# xbee_reciever_and_main.net
KiCad netlist of a schematic drawn in Altium Designer
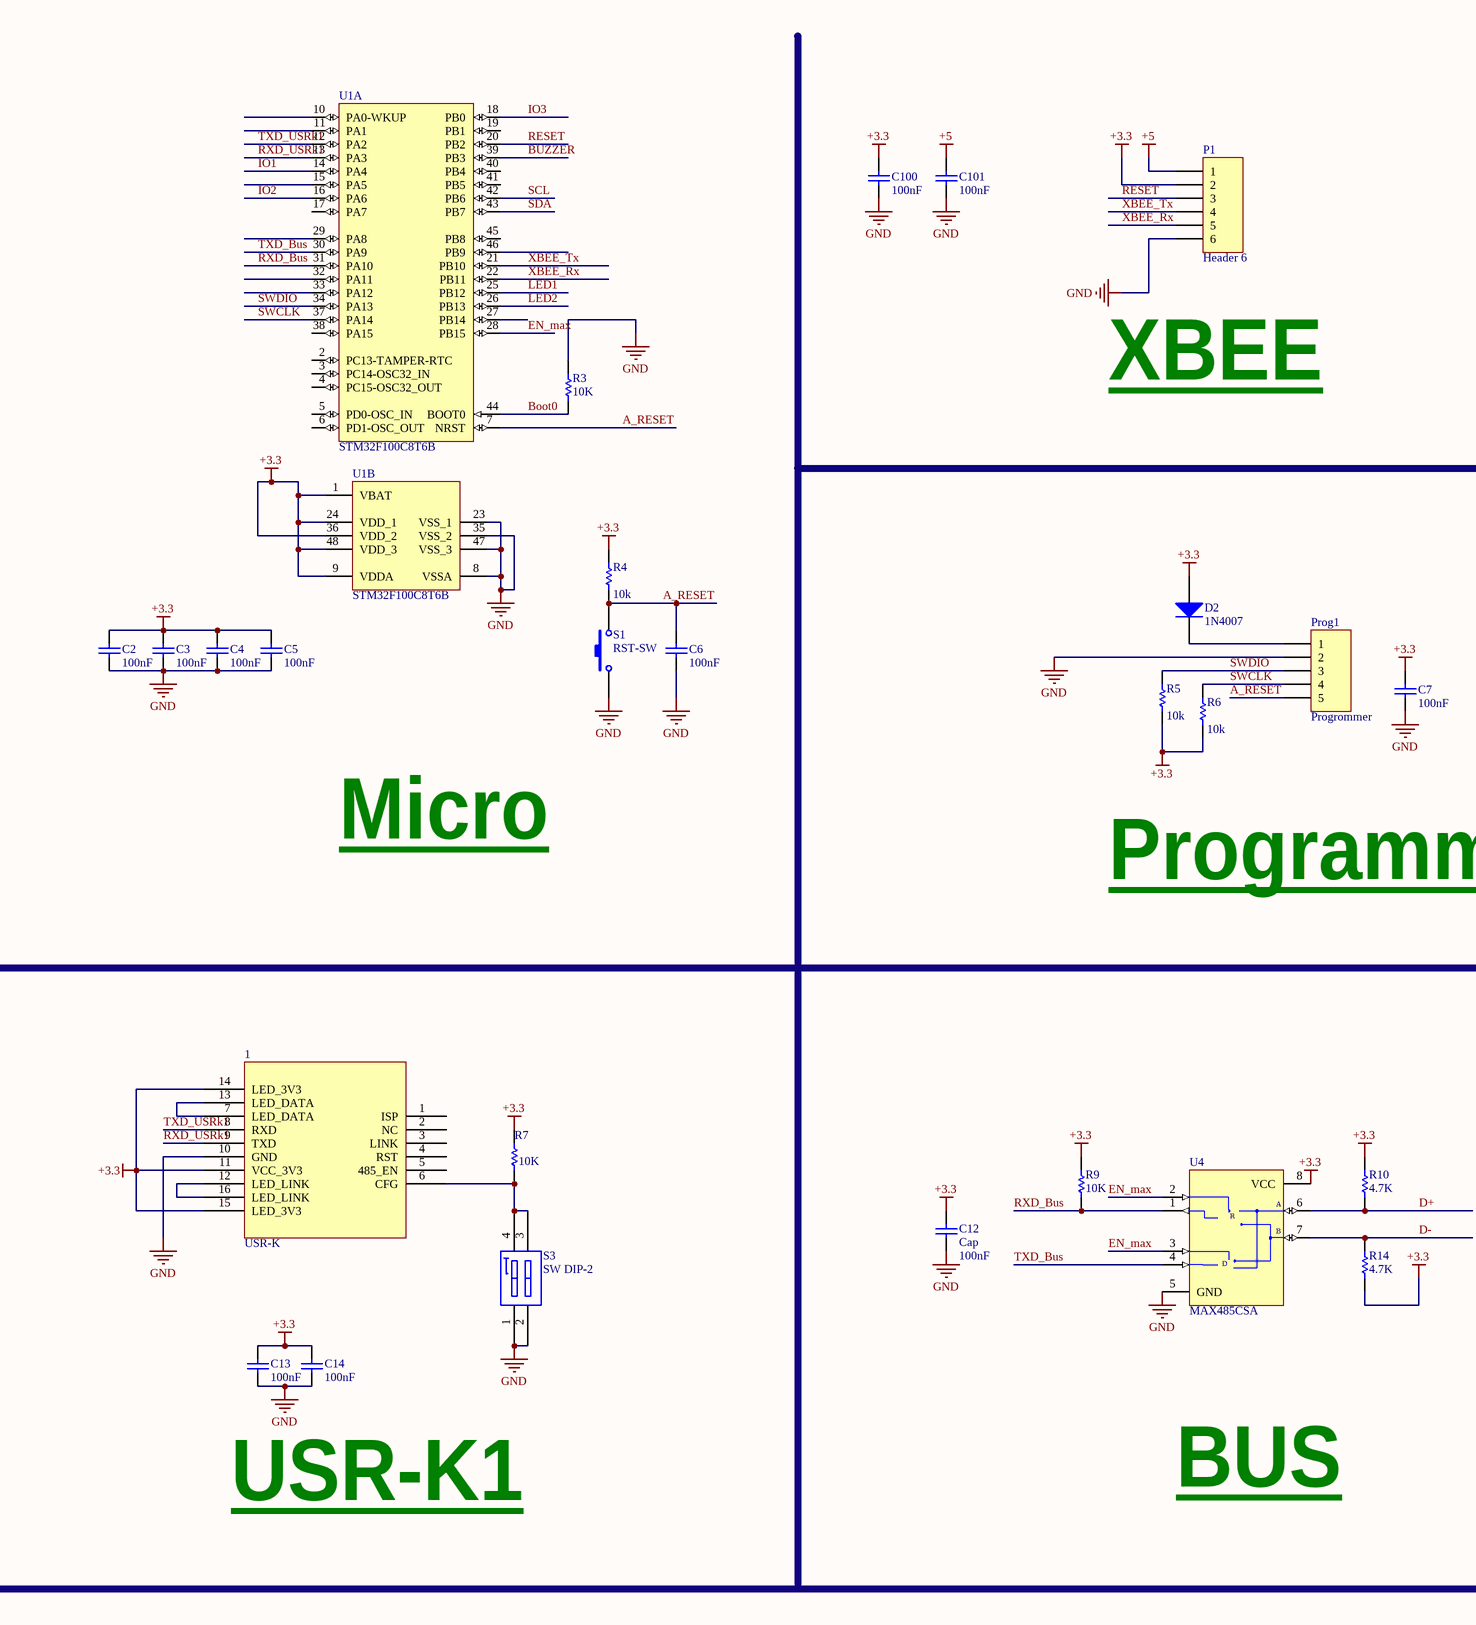
[diagram p0: xbee reciever and main.SchDoc, left]
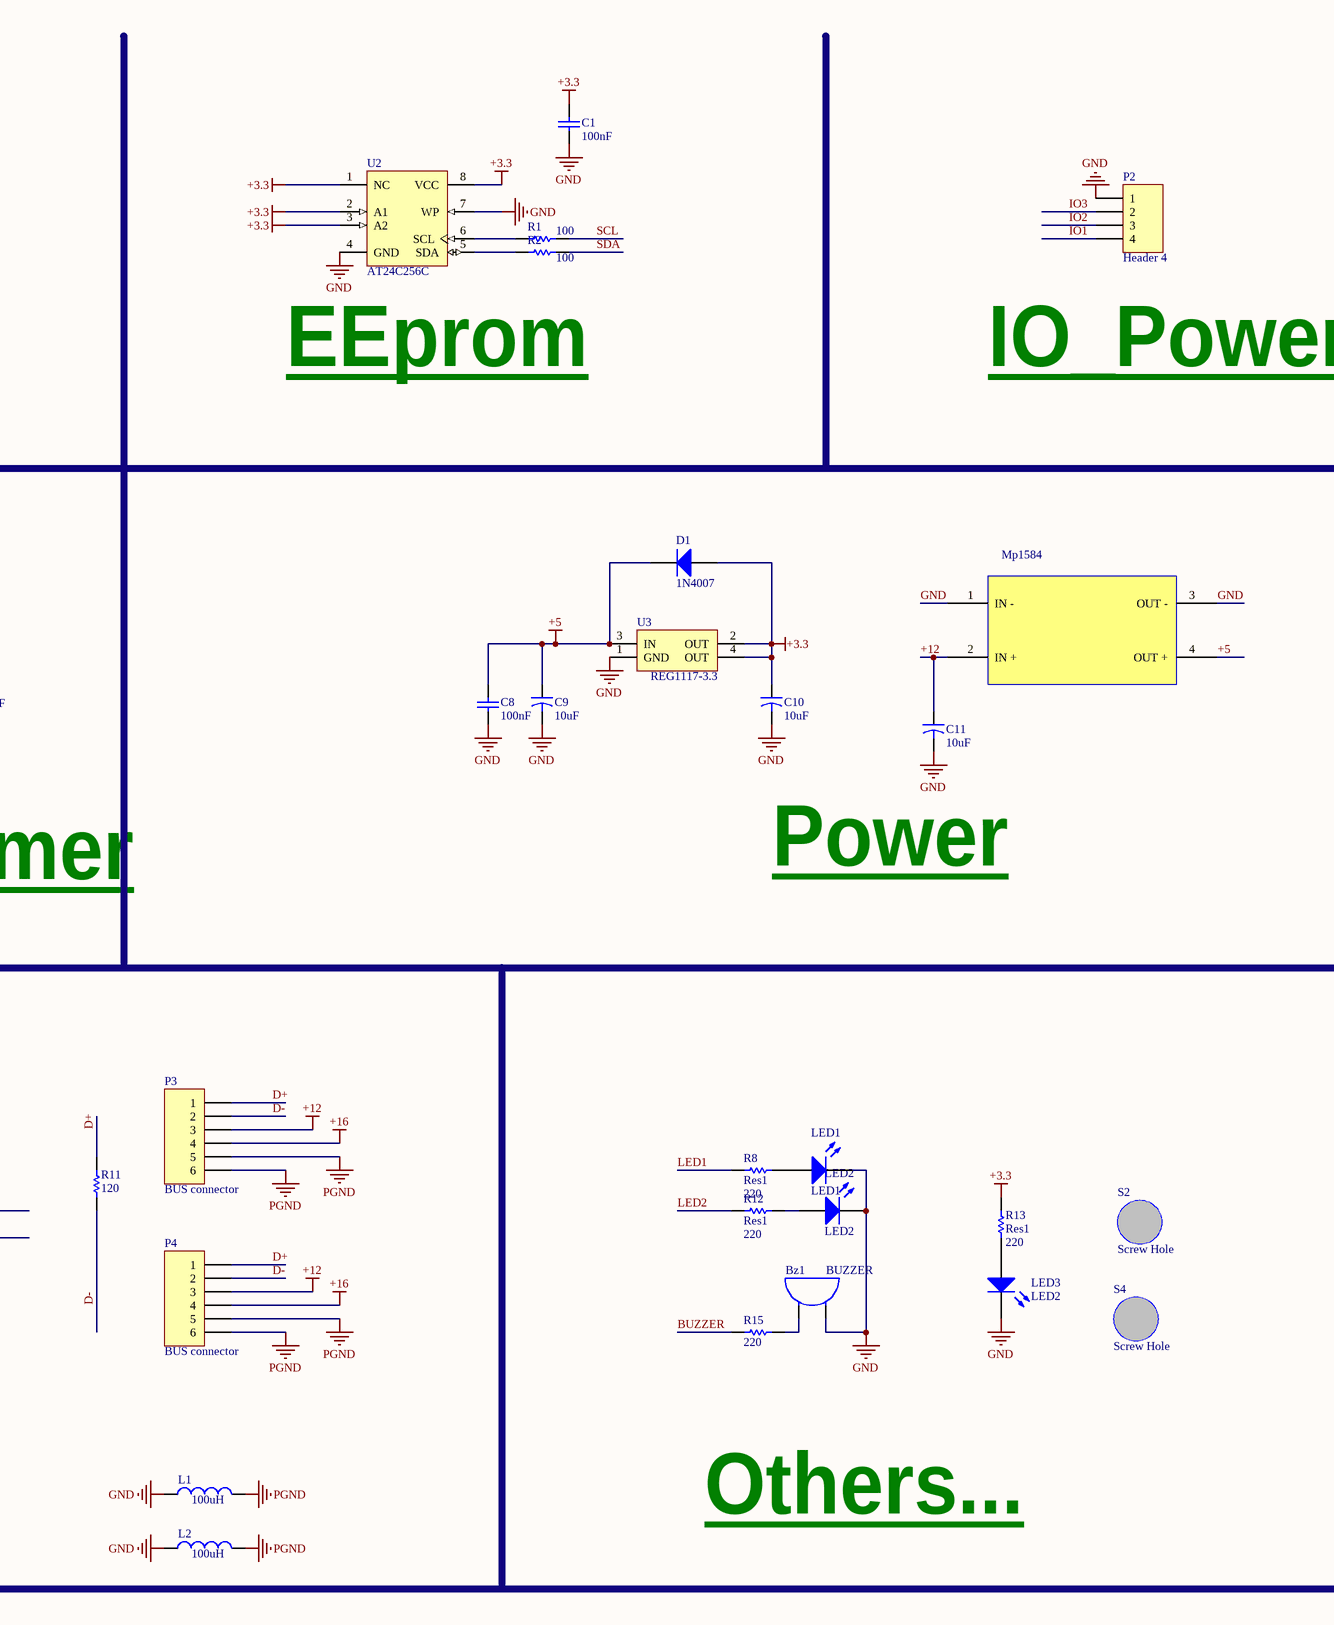
[diagram p1: xbee reciever and main.SchDoc, right]

(export (version "E")
  (design (tool "Eeschema 10.0.6"))
  (components
    (comp (ref "1") (value "USR-K") (footprint "USR-K1") (libsource (lib "USR-K1") (part "USR-K")))
    (comp (ref "Bz1") (value "BUZZER") (footprint "BUZZER") (libsource (lib "Device") (part "BUZZER")))
    (comp (ref "C1")
      (value "100nF")
      (footprint "1608[0603]")
      (description "Capacitor")
      (fields
        (field (name "MANUFACTURER") "Generic Components")
        (field (name "PUBLISHER") "Altium Hobart Technology Centre")
      )
      (libsource (lib "Miscellaneous Devices") (part "Cap"))
    )
    (comp (ref "C2")
      (value "100nF")
      (footprint "1608[0603]")
      (description "Capacitor")
      (fields
        (field (name "MANUFACTURER") "Generic Components")
        (field (name "PUBLISHER") "Altium Hobart Technology Centre")
      )
      (libsource (lib "Miscellaneous Devices") (part "Cap"))
    )
    (comp (ref "C3")
      (value "100nF")
      (footprint "1608[0603]")
      (description "Capacitor")
      (fields
        (field (name "MANUFACTURER") "Generic Components")
        (field (name "PUBLISHER") "Altium Hobart Technology Centre")
      )
      (libsource (lib "Miscellaneous Devices") (part "Cap"))
    )
    (comp (ref "C4")
      (value "100nF")
      (footprint "1608[0603]")
      (description "Capacitor")
      (fields
        (field (name "MANUFACTURER") "Generic Components")
        (field (name "PUBLISHER") "Altium Hobart Technology Centre")
      )
      (libsource (lib "Miscellaneous Devices") (part "Cap"))
    )
    (comp (ref "C5")
      (value "100nF")
      (footprint "1608[0603]")
      (description "Capacitor")
      (fields
        (field (name "MANUFACTURER") "Generic Components")
        (field (name "PUBLISHER") "Altium Hobart Technology Centre")
      )
      (libsource (lib "Miscellaneous Devices") (part "Cap"))
    )
    (comp (ref "C6")
      (value "100nF")
      (footprint "1608[0603]")
      (description "Capacitor")
      (fields
        (field (name "MANUFACTURER") "Generic Components")
        (field (name "PUBLISHER") "Altium Hobart Technology Centre")
      )
      (libsource (lib "Miscellaneous Devices") (part "Cap"))
    )
    (comp (ref "C7")
      (value "100nF")
      (footprint "j1-0603")
      (description "Capacitor")
      (fields
        (field (name "MANUFACTURER") "Generic Components")
        (field (name "PUBLISHER") "Altium Hobart Technology Centre")
      )
      (libsource (lib "Miscellaneous Devices") (part "Cap"))
    )
    (comp (ref "C8")
      (value "100nF")
      (footprint "J1-0603")
      (description "Capacitor")
      (fields (field (name "PUBLISHER") "Altium Limited"))
      (libsource (lib "Miscellaneous Devices") (part "Cap"))
    )
    (comp (ref "C9")
      (value "10uF")
      (footprint "2012[0805]")
      (description "Capacitor")
      (fields (field (name "Comment") "Cap_El") (field (name "PUBLISHER") "Altium Limited"))
      (libsource (lib "KN2CLib") (part "Cap_El"))
    )
    (comp (ref "C10")
      (value "10uF")
      (footprint "2012[0805]")
      (description "Capacitor")
      (fields (field (name "Comment") "Cap_El") (field (name "PUBLISHER") "Altium Limited"))
      (libsource (lib "KN2CLib") (part "Cap_El"))
    )
    (comp (ref "C11")
      (value "10uF")
      (footprint "2012[0805]")
      (description "Capacitor")
      (fields (field (name "Comment") "Cap_El") (field (name "PUBLISHER") "Altium Limited"))
      (libsource (lib "KN2CLib") (part "Cap_El"))
    )
    (comp (ref "C12")
      (value "Cap")
      (footprint "j1-0603")
      (description "Capacitor")
      (fields (field (name "ALTIUM_VALUE") "100nF") (field (name "PUBLISHER") "Altium Limited"))
      (libsource (lib "Miscellaneous Devices") (part "Cap"))
    )
    (comp (ref "C13")
      (value "100nF")
      (footprint "J1-0603")
      (description "Capacitor")
      (fields (field (name "PUBLISHER") "Altium Limited"))
      (libsource (lib "Miscellaneous Devices") (part "Cap"))
    )
    (comp (ref "C14")
      (value "100nF")
      (footprint "J1-0603")
      (description "Capacitor")
      (fields (field (name "PUBLISHER") "Altium Limited"))
      (libsource (lib "Miscellaneous Devices") (part "Cap"))
    )
    (comp (ref "C100")
      (value "100nF")
      (footprint "1608[0603]")
      (description "Capacitor")
      (fields
        (field (name "MANUFACTURER") "Generic Components")
        (field (name "PUBLISHER") "Altium Hobart Technology Centre")
      )
      (libsource (lib "Miscellaneous Devices") (part "Cap"))
    )
    (comp (ref "C101")
      (value "100nF")
      (footprint "1608[0603]")
      (description "Capacitor")
      (fields
        (field (name "MANUFACTURER") "Generic Components")
        (field (name "PUBLISHER") "Altium Hobart Technology Centre")
      )
      (libsource (lib "Miscellaneous Devices") (part "Cap"))
    )
    (comp (ref "D1")
      (value "1N4007")
      (footprint "US1M")
      (description "1 Amp General Purpose Rectifier")
      (fields (field (name "PUBLISHER") "Altium Limited"))
      (libsource (lib "KN2CLib") (part "Diode"))
    )
    (comp (ref "D2")
      (value "1N4007")
      (footprint "US1M")
      (description "1 Amp General Purpose Rectifier")
      (fields (field (name "PUBLISHER") "Altium Limited"))
      (libsource (lib "KN2CLib") (part "Diode"))
    )
    (comp (ref "L1")
      (value "100uH")
      (footprint "2012[0805]")
      (description "Inductor")
      (fields
        (field (name "MANUFACTURER") "Generic Components")
        (field (name "PUBLISHER") "Altium Hobart Technology Centre")
      )
      (libsource (lib "Miscellaneous Devices") (part "Inductor"))
    )
    (comp (ref "L2")
      (value "100uH")
      (footprint "2012[0805]")
      (description "Inductor")
      (fields
        (field (name "MANUFACTURER") "Generic Components")
        (field (name "PUBLISHER") "Altium Hobart Technology Centre")
      )
      (libsource (lib "Miscellaneous Devices") (part "Inductor"))
    )
    (comp (ref "LED1")
      (value "LED1")
      (footprint "3518")
      (description "Typical BLUE SiC LED")
      (fields (field (name "PUBLISHER") "Altium Limited"))
      (libsource (lib "Miscellaneous Devices") (part "LED3"))
    )
    (comp (ref "LED2")
      (value "LED2")
      (footprint "3518")
      (description "Typical BLUE SiC LED")
      (fields (field (name "PUBLISHER") "Altium Limited"))
      (libsource (lib "Miscellaneous Devices") (part "LED3"))
    )
    (comp (ref "LED3")
      (value "LED2")
      (footprint "3518")
      (description "Typical BLUE SiC LED")
      (fields (field (name "PUBLISHER") "Altium Limited"))
      (libsource (lib "Miscellaneous Devices") (part "LED3"))
    )
    (comp (ref "Mp1") (value "Mp1584") (footprint "mp1584-1.8") (libsource (lib "mehdi2309") (part "Mp1584")))
    (comp (ref "P1")
      (value "Header 6")
      (footprint "HDR1X6")
      (description "Header, 6-Pin")
      (fields (field (name "PUBLISHER") "Altium Limited"))
      (libsource (lib "") (part "Header 6_1"))
    )
    (comp (ref "P2")
      (value "Header 4")
      (footprint "JP circular 4")
      (description "Header, 4-Pin")
      (fields (field (name "PUBLISHER") "Altium Limited"))
      (libsource (lib "Miscellaneous Connectors") (part "Header 4"))
    )
    (comp (ref "P3")
      (value "BUS connector")
      (footprint "CON6-TIWAN")
      (description "Header, 6-Pin")
      (fields (field (name "PUBLISHER") "Altium Limited"))
      (libsource (lib "Miscellaneous Connectors") (part "Header 6"))
    )
    (comp (ref "P4")
      (value "BUS connector")
      (footprint "con6-tiwan")
      (description "Header, 6-Pin")
      (fields (field (name "PUBLISHER") "Altium Limited"))
      (libsource (lib "Miscellaneous Connectors") (part "Header 6"))
    )
    (comp (ref "Prog1")
      (value "Progrommer")
      (footprint "HDR1x5")
      (description "Header, 5-Pin")
      (fields (field (name "PUBLISHER") "Altium Limited"))
      (libsource (lib "Miscellaneous Connectors") (part "Header 5"))
    )
    (comp (ref "R1")
      (value "100")
      (footprint "j1-0603")
      (description "Resistor")
      (fields (field (name "Comment") "Res1") (field (name "PUBLISHER") "Altium Limited"))
      (libsource (lib "Miscellaneous Devices") (part "Res1"))
    )
    (comp (ref "R2")
      (value "100")
      (footprint "j1-0603")
      (description "Resistor")
      (fields (field (name "Comment") "Res1") (field (name "PUBLISHER") "Altium Limited"))
      (libsource (lib "Miscellaneous Devices") (part "Res1"))
    )
    (comp (ref "R3")
      (value "10K")
      (footprint "J1-0603")
      (description "Resistor")
      (fields (field (name "PUBLISHER") "Altium Limited"))
      (libsource (lib "Miscellaneous Devices") (part "Res1"))
    )
    (comp (ref "R4")
      (value "10k")
      (footprint "J1-0603")
      (description "Semiconductor Resistor")
      (fields (field (name "PUBLISHER") "Altium Limited"))
      (libsource (lib "KN2CLib") (part "Res"))
    )
    (comp (ref "R5")
      (value "10k")
      (footprint "J1-0603")
      (description "Semiconductor Resistor")
      (fields (field (name "PUBLISHER") "Altium Limited"))
      (libsource (lib "KN2CLib") (part "Res"))
    )
    (comp (ref "R6")
      (value "10k")
      (footprint "J1-0603")
      (description "Semiconductor Resistor")
      (fields (field (name "PUBLISHER") "Altium Limited"))
      (libsource (lib "KN2CLib") (part "Res"))
    )
    (comp (ref "R7")
      (value "10K")
      (footprint "J1-0603")
      (description "Resistor")
      (fields (field (name "PUBLISHER") "Altium Limited"))
      (libsource (lib "Miscellaneous Devices") (part "Res1"))
    )
    (comp (ref "R8")
      (value "Res1")
      (footprint "j1-0603")
      (description "Resistor")
      (fields (field (name "ALTIUM_VALUE") "220") (field (name "PUBLISHER") "Altium Limited"))
      (libsource (lib "Miscellaneous Devices") (part "Res1"))
    )
    (comp (ref "R9")
      (value "10K")
      (footprint "j1-0603")
      (description "Resistor")
      (fields (field (name "Comment") "Res1") (field (name "PUBLISHER") "Altium Limited"))
      (libsource (lib "Miscellaneous Devices") (part "Res1"))
    )
    (comp (ref "R10")
      (value "4.7K")
      (footprint "j1-0603")
      (description "Resistor")
      (fields (field (name "Comment") "Res1") (field (name "PUBLISHER") "Altium Limited"))
      (libsource (lib "Miscellaneous Devices") (part "Res1"))
    )
    (comp (ref "R11")
      (value "120")
      (footprint "j1-0603")
      (description "Resistor")
      (fields (field (name "Comment") "Res1") (field (name "PUBLISHER") "Altium Limited"))
      (libsource (lib "Miscellaneous Devices") (part "Res1"))
    )
    (comp (ref "R12")
      (value "Res1")
      (footprint "j1-0603")
      (description "Resistor")
      (fields (field (name "ALTIUM_VALUE") "220") (field (name "PUBLISHER") "Altium Limited"))
      (libsource (lib "Miscellaneous Devices") (part "Res1"))
    )
    (comp (ref "R13")
      (value "Res1")
      (footprint "j1-0603")
      (description "Resistor")
      (fields (field (name "ALTIUM_VALUE") "220") (field (name "PUBLISHER") "Altium Limited"))
      (libsource (lib "Miscellaneous Devices") (part "Res1"))
    )
    (comp (ref "R14")
      (value "4.7K")
      (footprint "j1-0603")
      (description "Resistor")
      (fields (field (name "Comment") "Res1") (field (name "PUBLISHER") "Altium Limited"))
      (libsource (lib "Miscellaneous Devices") (part "Res1"))
    )
    (comp (ref "R15")
      (value "220")
      (footprint "j1-0603")
      (description "Resistor")
      (fields (field (name "PUBLISHER") "Altium Limited"))
      (libsource (lib "Miscellaneous Devices") (part "Res1"))
    )
    (comp (ref "S1")
      (value "RST-SW")
      (footprint "SW-PB-4P")
      (description "Switch")
      (fields (field (name "PUBLISHER") "Altium Limited"))
      (libsource (lib "Miscellaneous Devices") (part "SW-PB"))
    )
    (comp (ref "S2")
      (value "Screw Hole")
      (footprint "Screw Holw 3-6 mm")
      (libsource (lib "KN2CLib") (part "Screw Hole"))
    )
    (comp (ref "S3") (value "SW DIP-2") (footprint "SMD-4") (libsource (lib "Device") (part "SW DIP-2")))
    (comp (ref "S4")
      (value "Screw Hole")
      (footprint "Screw Holw 3-6 mm")
      (libsource (lib "KN2CLib") (part "Screw Hole"))
    )
    (comp (ref "U1")
      (value "STM32F100C8T6B")
      (footprint "STM-LQFP48_L")
      (libsource (lib "STMicroelectronics STM32 F1") (part "STM32F100C8T6B"))
    )
    (comp (ref "U2")
      (value "AT24C256C")
      (footprint "8S1_N")
      (description "4Kbit (512 x 8), 2-wire Bus Automotive Serial EEPROM with Write Protect, 2.5V, 8-Pin SOIC, Bulk")
      (fields (field (name "PUBLISHER") "Altium Limited"))
      (libsource (lib "Atmel Memory Serial EEPROM") (part "AT24C04BN-SP25-B"))
    )
    (comp (ref "U3")
      (value "REG1117-3.3")
      (footprint "SOT223")
      (description "800mA and 1A Low Dropout Positive Regulator 2.85V, 3.3V, 5V, and Adjustable")
      (fields (field (name "PUBLISHER") "Altium Limited"))
      (libsource (lib "BB Power Mgt Voltage Regulator") (part "REG1117-3.3"))
    )
    (comp (ref "U4")
      (value "MAX485CSA")
      (footprint "NSO8_N")
      (description "Low-Power, Slew-Rate-Limited RS-485/RS-422 Transceiver")
      (fields (field (name "PUBLISHER") "Altium Limited"))
      (libsource (lib "Maxim Communication Transceiver") (part "MAX485CSA"))
    )
  )
  (nets
    (net (code "1") (name "+3.3") (class "Default")
      (node (ref "1") (pin "11") (pinfunction "VCC_3V3_11") (pintype "passive"))
      (node (ref "1") (pin "14") (pinfunction "LED_3V3_14") (pintype "passive"))
      (node (ref "1") (pin "15") (pinfunction "LED_3V3_15") (pintype "passive"))
      (node (ref "C1") (pin "2") (pinfunction "2_2") (pintype "passive"))
      (node (ref "C10") (pin "1") (pinfunction "1_1") (pintype "passive"))
      (node (ref "C100") (pin "2") (pinfunction "2_2") (pintype "passive"))
      (node (ref "C12") (pin "2") (pinfunction "2_2") (pintype "passive"))
      (node (ref "C13") (pin "2") (pinfunction "2_2") (pintype "passive"))
      (node (ref "C14") (pin "2") (pinfunction "2_2") (pintype "passive"))
      (node (ref "C2") (pin "2") (pinfunction "2_2") (pintype "passive"))
      (node (ref "C3") (pin "2") (pinfunction "2_2") (pintype "passive"))
      (node (ref "C4") (pin "2") (pinfunction "2_2") (pintype "passive"))
      (node (ref "C5") (pin "2") (pinfunction "2_2") (pintype "passive"))
      (node (ref "C7") (pin "2") (pinfunction "2_2") (pintype "passive"))
      (node (ref "D1") (pin "1") (pinfunction "A_1") (pintype "passive"))
      (node (ref "D2") (pin "1") (pinfunction "A_1") (pintype "passive"))
      (node (ref "P1") (pin "2") (pinfunction "2_2") (pintype "passive"))
      (node (ref "R10") (pin "1") (pinfunction "1_1") (pintype "passive"))
      (node (ref "R13") (pin "1") (pinfunction "1_1") (pintype "passive"))
      (node (ref "R14") (pin "2") (pinfunction "2_2") (pintype "passive"))
      (node (ref "R4") (pin "1") (pinfunction "1_1") (pintype "passive"))
      (node (ref "R5") (pin "2") (pinfunction "2_2") (pintype "passive"))
      (node (ref "R6") (pin "2") (pinfunction "2_2") (pintype "passive"))
      (node (ref "R7") (pin "2") (pinfunction "2_2") (pintype "passive"))
      (node (ref "R9") (pin "1") (pinfunction "1_1") (pintype "passive"))
      (node (ref "U1") (pin "1") (pinfunction "VBAT_1") (pintype "power_in"))
      (node (ref "U1") (pin "24") (pinfunction "VDD_1_24") (pintype "power_in"))
      (node (ref "U1") (pin "36") (pinfunction "VDD_2_36") (pintype "power_in"))
      (node (ref "U1") (pin "48") (pinfunction "VDD_3_48") (pintype "power_in"))
      (node (ref "U1") (pin "9") (pinfunction "VDDA_9") (pintype "power_in"))
      (node (ref "U2") (pin "1") (pinfunction "NC_1") (pintype "passive"))
      (node (ref "U2") (pin "2") (pinfunction "A1_2") (pintype "input"))
      (node (ref "U2") (pin "3") (pinfunction "A2_3") (pintype "input"))
      (node (ref "U2") (pin "8") (pinfunction "VCC_8") (pintype "power_in"))
      (node (ref "U3") (pin "2") (pinfunction "OUT_2") (pintype "power_in"))
      (node (ref "U3") (pin "4") (pinfunction "OUT_4") (pintype "power_in"))
      (node (ref "U4") (pin "8") (pinfunction "VCC_8") (pintype "power_in"))
    )
    (net (code "2") (name "+5") (class "Default")
      (node (ref "C101") (pin "2") (pinfunction "2_2") (pintype "passive"))
      (node (ref "C8") (pin "2") (pinfunction "2_2") (pintype "passive"))
      (node (ref "C9") (pin "1") (pinfunction "1_1") (pintype "passive"))
      (node (ref "D1") (pin "2") (pinfunction "K_2") (pintype "passive"))
      (node (ref "Mp1") (pin "4") (pinfunction "OUT_+_4") (pintype "passive"))
      (node (ref "P1") (pin "1") (pinfunction "1_1") (pintype "passive"))
      (node (ref "U3") (pin "3") (pinfunction "IN_3") (pintype "power_in"))
    )
    (net (code "3") (name "+12") (class "Default")
      (node (ref "C11") (pin "1") (pinfunction "1_1") (pintype "passive"))
      (node (ref "Mp1") (pin "2") (pinfunction "IN_+_2") (pintype "passive"))
      (node (ref "P3") (pin "3") (pinfunction "3_3") (pintype "passive"))
      (node (ref "P4") (pin "3") (pinfunction "3_3") (pintype "passive"))
    )
    (net (code "4") (name "+16") (class "Default")
      (node (ref "P3") (pin "4") (pinfunction "4_4") (pintype "passive"))
      (node (ref "P4") (pin "4") (pinfunction "4_4") (pintype "passive"))
    )
    (net (code "5") (name "/A_RESET") (class "Default")
      (node (ref "C6") (pin "2") (pinfunction "2_2") (pintype "passive"))
      (node (ref "Prog1") (pin "5") (pinfunction "5_5") (pintype "passive"))
      (node (ref "R4") (pin "2") (pinfunction "2_2") (pintype "passive"))
      (node (ref "S1") (pin "2") (pinfunction "2_2") (pintype "passive"))
      (node (ref "U1") (pin "7") (pinfunction "NRST_7") (pintype "bidirectional"))
    )
    (net (code "6") (name "/BUZZER") (class "Default")
      (node (ref "R15") (pin "1") (pinfunction "1_1") (pintype "passive"))
      (node (ref "U1") (pin "39") (pinfunction "PB3_39") (pintype "bidirectional"))
    )
    (net (code "7") (name "/Boot0") (class "Default")
      (node (ref "R3") (pin "2") (pinfunction "2_2") (pintype "passive"))
      (node (ref "U1") (pin "44") (pinfunction "BOOT0_44") (pintype "input"))
    )
    (net (code "8") (name "/D+") (class "Default")
      (node (ref "P3") (pin "1") (pinfunction "1_1") (pintype "passive"))
      (node (ref "P4") (pin "1") (pinfunction "1_1") (pintype "passive"))
      (node (ref "R10") (pin "2") (pinfunction "2_2") (pintype "passive"))
      (node (ref "R11") (pin "1") (pinfunction "1_1") (pintype "passive"))
      (node (ref "U4") (pin "6") (pinfunction "A_6") (pintype "bidirectional"))
    )
    (net (code "9") (name "/D-") (class "Default")
      (node (ref "P3") (pin "2") (pinfunction "2_2") (pintype "passive"))
      (node (ref "P4") (pin "2") (pinfunction "2_2") (pintype "passive"))
      (node (ref "R11") (pin "2") (pinfunction "2_2") (pintype "passive"))
      (node (ref "R14") (pin "1") (pinfunction "1_1") (pintype "passive"))
      (node (ref "U4") (pin "7") (pinfunction "B_7") (pintype "bidirectional"))
    )
    (net (code "10") (name "/EN_max") (class "Default")
      (node (ref "U1") (pin "28") (pinfunction "PB15_28") (pintype "bidirectional"))
      (node (ref "U4") (pin "2") (pinfunction "~{RE}_2") (pintype "input"))
      (node (ref "U4") (pin "3") (pinfunction "DE_3") (pintype "input"))
    )
    (net (code "11") (name "/IO1") (class "Default")
      (node (ref "P2") (pin "4") (pinfunction "4_4") (pintype "passive"))
      (node (ref "U1") (pin "14") (pinfunction "PA4_14") (pintype "bidirectional"))
    )
    (net (code "12") (name "/IO2") (class "Default")
      (node (ref "P2") (pin "3") (pinfunction "3_3") (pintype "passive"))
      (node (ref "U1") (pin "16") (pinfunction "PA6_16") (pintype "bidirectional"))
    )
    (net (code "13") (name "/IO3") (class "Default")
      (node (ref "P2") (pin "2") (pinfunction "2_2") (pintype "passive"))
      (node (ref "U1") (pin "18") (pinfunction "PB0_18") (pintype "bidirectional"))
    )
    (net (code "14") (name "/LED1") (class "Default")
      (node (ref "R8") (pin "1") (pinfunction "1_1") (pintype "passive"))
      (node (ref "U1") (pin "25") (pinfunction "PB12_25") (pintype "bidirectional"))
    )
    (net (code "15") (name "/LED2") (class "Default")
      (node (ref "R12") (pin "1") (pinfunction "1_1") (pintype "passive"))
      (node (ref "U1") (pin "26") (pinfunction "PB13_26") (pintype "bidirectional"))
    )
    (net (code "16") (name "/RESET") (class "Default")
      (node (ref "P1") (pin "3") (pinfunction "3_3") (pintype "passive"))
      (node (ref "U1") (pin "20") (pinfunction "PB2_20") (pintype "bidirectional"))
    )
    (net (code "17") (name "/RXD_Bus") (class "Default")
      (node (ref "R9") (pin "2") (pinfunction "2_2") (pintype "passive"))
      (node (ref "U1") (pin "31") (pinfunction "PA10_31") (pintype "bidirectional"))
      (node (ref "U4") (pin "1") (pinfunction "RO_1") (pintype "output"))
    )
    (net (code "18") (name "/RXD_USRk1") (class "Default")
      (node (ref "1") (pin "9") (pinfunction "TXD_9") (pintype "passive"))
      (node (ref "U1") (pin "13") (pinfunction "PA3_13") (pintype "bidirectional"))
    )
    (net (code "19") (name "/SCL") (class "Default")
      (node (ref "R1") (pin "2") (pinfunction "2_2") (pintype "passive"))
      (node (ref "U1") (pin "42") (pinfunction "PB6_42") (pintype "bidirectional"))
    )
    (net (code "20") (name "/SDA") (class "Default")
      (node (ref "R2") (pin "2") (pinfunction "2_2") (pintype "passive"))
      (node (ref "U1") (pin "43") (pinfunction "PB7_43") (pintype "bidirectional"))
    )
    (net (code "21") (name "/SWCLK") (class "Default")
      (node (ref "Prog1") (pin "4") (pinfunction "4_4") (pintype "passive"))
      (node (ref "R6") (pin "1") (pinfunction "1_1") (pintype "passive"))
      (node (ref "U1") (pin "37") (pinfunction "PA14_37") (pintype "bidirectional"))
    )
    (net (code "22") (name "/SWDIO") (class "Default")
      (node (ref "Prog1") (pin "3") (pinfunction "3_3") (pintype "passive"))
      (node (ref "R5") (pin "1") (pinfunction "1_1") (pintype "passive"))
      (node (ref "U1") (pin "34") (pinfunction "PA13_34") (pintype "bidirectional"))
    )
    (net (code "23") (name "/TXD_Bus") (class "Default")
      (node (ref "U1") (pin "30") (pinfunction "PA9_30") (pintype "bidirectional"))
      (node (ref "U4") (pin "4") (pinfunction "DI_4") (pintype "input"))
    )
    (net (code "24") (name "/TXD_USRk1") (class "Default")
      (node (ref "1") (pin "8") (pinfunction "RXD_8") (pintype "passive"))
      (node (ref "U1") (pin "12") (pinfunction "PA2_12") (pintype "bidirectional"))
    )
    (net (code "25") (name "/XBEE_Rx") (class "Default")
      (node (ref "P1") (pin "5") (pinfunction "5_5") (pintype "passive"))
      (node (ref "U1") (pin "22") (pinfunction "PB11_22") (pintype "bidirectional"))
    )
    (net (code "26") (name "/XBEE_Tx") (class "Default")
      (node (ref "P1") (pin "4") (pinfunction "4_4") (pintype "passive"))
      (node (ref "U1") (pin "21") (pinfunction "PB10_21") (pintype "bidirectional"))
    )
    (net (code "27") (name "GND") (class "Default")
      (node (ref "1") (pin "10") (pinfunction "GND_10") (pintype "passive"))
      (node (ref "Bz1") (pin "2") (pintype "passive"))
      (node (ref "C1") (pin "1") (pinfunction "1_1") (pintype "passive"))
      (node (ref "C10") (pin "2") (pinfunction "2_2") (pintype "passive"))
      (node (ref "C100") (pin "1") (pinfunction "1_1") (pintype "passive"))
      (node (ref "C101") (pin "1") (pinfunction "1_1") (pintype "passive"))
      (node (ref "C11") (pin "2") (pinfunction "2_2") (pintype "passive"))
      (node (ref "C12") (pin "1") (pinfunction "1_1") (pintype "passive"))
      (node (ref "C13") (pin "1") (pinfunction "1_1") (pintype "passive"))
      (node (ref "C14") (pin "1") (pinfunction "1_1") (pintype "passive"))
      (node (ref "C2") (pin "1") (pinfunction "1_1") (pintype "passive"))
      (node (ref "C3") (pin "1") (pinfunction "1_1") (pintype "passive"))
      (node (ref "C4") (pin "1") (pinfunction "1_1") (pintype "passive"))
      (node (ref "C5") (pin "1") (pinfunction "1_1") (pintype "passive"))
      (node (ref "C6") (pin "1") (pinfunction "1_1") (pintype "passive"))
      (node (ref "C7") (pin "1") (pinfunction "1_1") (pintype "passive"))
      (node (ref "C8") (pin "1") (pinfunction "1_1") (pintype "passive"))
      (node (ref "C9") (pin "2") (pinfunction "2_2") (pintype "passive"))
      (node (ref "L1") (pin "1") (pinfunction "1_1") (pintype "passive"))
      (node (ref "L2") (pin "1") (pinfunction "1_1") (pintype "passive"))
      (node (ref "LED1") (pin "2") (pinfunction "K_2") (pintype "passive"))
      (node (ref "LED2") (pin "2") (pinfunction "K_2") (pintype "passive"))
      (node (ref "LED3") (pin "2") (pinfunction "K_2") (pintype "passive"))
      (node (ref "Mp1") (pin "1") (pinfunction "IN_-_1") (pintype "passive"))
      (node (ref "Mp1") (pin "3") (pinfunction "OUT_-_3") (pintype "passive"))
      (node (ref "P1") (pin "6") (pinfunction "6_6") (pintype "passive"))
      (node (ref "P2") (pin "1") (pinfunction "1_1") (pintype "passive"))
      (node (ref "Prog1") (pin "2") (pinfunction "2_2") (pintype "passive"))
      (node (ref "R3") (pin "1") (pinfunction "1_1") (pintype "passive"))
      (node (ref "S1") (pin "1") (pinfunction "1_1") (pintype "passive"))
      (node (ref "S3") (pin "1") (pinfunction "A1_1") (pintype "passive"))
      (node (ref "S3") (pin "2") (pinfunction "A2_2") (pintype "passive"))
      (node (ref "U1") (pin "23") (pinfunction "VSS_1_23") (pintype "power_in"))
      (node (ref "U1") (pin "35") (pinfunction "VSS_2_35") (pintype "power_in"))
      (node (ref "U1") (pin "47") (pinfunction "VSS_3_47") (pintype "power_in"))
      (node (ref "U1") (pin "8") (pinfunction "VSSA_8") (pintype "power_in"))
      (node (ref "U2") (pin "4") (pinfunction "GND_4") (pintype "power_in"))
      (node (ref "U2") (pin "7") (pinfunction "WP_7") (pintype "input"))
      (node (ref "U3") (pin "1") (pinfunction "GND_1") (pintype "power_in"))
      (node (ref "U4") (pin "5") (pinfunction "GND_5") (pintype "power_in"))
    )
    (net (code "28") (name "Net-(1-CFG)") (class "Default")
      (node (ref "1") (pin "6") (pinfunction "CFG_6") (pintype "passive"))
      (node (ref "R7") (pin "1") (pinfunction "1_1") (pintype "passive"))
      (node (ref "S3") (pin "3") (pinfunction "B2_3") (pintype "passive"))
      (node (ref "S3") (pin "4") (pinfunction "B1_4") (pintype "passive"))
    )
    (net (code "29") (name "Net-(1-LED_DATA-Pad13)") (class "Default")
      (node (ref "1") (pin "13") (pinfunction "LED_DATA_13") (pintype "passive"))
      (node (ref "1") (pin "7") (pinfunction "LED_DATA_7") (pintype "passive"))
    )
    (net (code "30") (name "Net-(1-LED_LINK-Pad12)") (class "Default")
      (node (ref "1") (pin "12") (pinfunction "LED_LINK_12") (pintype "passive"))
      (node (ref "1") (pin "16") (pinfunction "LED_LINK_16") (pintype "passive"))
    )
    (net (code "31") (name "Net-(Bz1-Pad1)") (class "Default")
      (node (ref "Bz1") (pin "1") (pintype "passive"))
      (node (ref "R15") (pin "2") (pinfunction "2_2") (pintype "passive"))
    )
    (net (code "32") (name "Net-(D2-K)") (class "Default")
      (node (ref "D2") (pin "2") (pinfunction "K_2") (pintype "passive"))
      (node (ref "Prog1") (pin "1") (pinfunction "1_1") (pintype "passive"))
    )
    (net (code "33") (name "Net-(LED1-A)") (class "Default")
      (node (ref "LED1") (pin "1") (pinfunction "A_1") (pintype "passive"))
      (node (ref "R8") (pin "2") (pinfunction "2_2") (pintype "passive"))
    )
    (net (code "34") (name "Net-(LED2-A)") (class "Default")
      (node (ref "LED2") (pin "1") (pinfunction "A_1") (pintype "passive"))
      (node (ref "R12") (pin "2") (pinfunction "2_2") (pintype "passive"))
    )
    (net (code "35") (name "Net-(LED3-A)") (class "Default")
      (node (ref "LED3") (pin "1") (pinfunction "A_1") (pintype "passive"))
      (node (ref "R13") (pin "2") (pinfunction "2_2") (pintype "passive"))
    )
    (net (code "36") (name "Net-(U2-SCL)") (class "Default")
      (node (ref "R1") (pin "1") (pinfunction "1_1") (pintype "passive"))
      (node (ref "U2") (pin "6") (pinfunction "SCL_6") (pintype "input"))
    )
    (net (code "37") (name "Net-(U2-SDA)") (class "Default")
      (node (ref "R2") (pin "1") (pinfunction "1_1") (pintype "passive"))
      (node (ref "U2") (pin "5") (pinfunction "SDA_5") (pintype "bidirectional"))
    )
    (net (code "38") (name "PGND") (class "Default")
      (node (ref "L1") (pin "2") (pinfunction "2_2") (pintype "passive"))
      (node (ref "L2") (pin "2") (pinfunction "2_2") (pintype "passive"))
      (node (ref "P3") (pin "5") (pinfunction "5_5") (pintype "passive"))
      (node (ref "P3") (pin "6") (pinfunction "6_6") (pintype "passive"))
      (node (ref "P4") (pin "5") (pinfunction "5_5") (pintype "passive"))
      (node (ref "P4") (pin "6") (pinfunction "6_6") (pintype "passive"))
    )
    (net (code "39") (name "unconnected-(1-485_EN-Pad5)") (class "Default")
      (node (ref "1") (pin "5") (pinfunction "485_EN_5") (pintype "passive"))
    )
    (net (code "40") (name "unconnected-(1-ISP-Pad1)") (class "Default")
      (node (ref "1") (pin "1") (pinfunction "ISP_1") (pintype "passive"))
    )
    (net (code "41") (name "unconnected-(1-LINK-Pad3)") (class "Default")
      (node (ref "1") (pin "3") (pinfunction "LINK_3") (pintype "passive"))
    )
    (net (code "42") (name "unconnected-(1-NC-Pad2)") (class "Default")
      (node (ref "1") (pin "2") (pinfunction "NC_2") (pintype "passive"))
    )
    (net (code "43") (name "unconnected-(1-RST-Pad4)") (class "Default")
      (node (ref "1") (pin "4") (pinfunction "RST_4") (pintype "passive"))
    )
    (net (code "44") (name "unconnected-(U1A-PA0-WKUP-Pad10)") (class "Default")
      (node (ref "U1") (pin "10") (pinfunction "PA0-WKUP_10") (pintype "bidirectional"))
    )
    (net (code "45") (name "unconnected-(U1A-PA1-Pad11)") (class "Default")
      (node (ref "U1") (pin "11") (pinfunction "PA1_11") (pintype "bidirectional"))
    )
    (net (code "46") (name "unconnected-(U1A-PA5-Pad15)") (class "Default")
      (node (ref "U1") (pin "15") (pinfunction "PA5_15") (pintype "bidirectional"))
    )
    (net (code "47") (name "unconnected-(U1A-PA7-Pad17)") (class "Default")
      (node (ref "U1") (pin "17") (pinfunction "PA7_17") (pintype "bidirectional"))
    )
    (net (code "48") (name "unconnected-(U1A-PA8-Pad29)") (class "Default")
      (node (ref "U1") (pin "29") (pinfunction "PA8_29") (pintype "bidirectional"))
    )
    (net (code "49") (name "unconnected-(U1A-PA11-Pad32)") (class "Default")
      (node (ref "U1") (pin "32") (pinfunction "PA11_32") (pintype "bidirectional"))
    )
    (net (code "50") (name "unconnected-(U1A-PA12-Pad33)") (class "Default")
      (node (ref "U1") (pin "33") (pinfunction "PA12_33") (pintype "bidirectional"))
    )
    (net (code "51") (name "unconnected-(U1A-PA15-Pad38)") (class "Default")
      (node (ref "U1") (pin "38") (pinfunction "PA15_38") (pintype "bidirectional"))
    )
    (net (code "52") (name "unconnected-(U1A-PB1-Pad19)") (class "Default")
      (node (ref "U1") (pin "19") (pinfunction "PB1_19") (pintype "bidirectional"))
    )
    (net (code "53") (name "unconnected-(U1A-PB4-Pad40)") (class "Default")
      (node (ref "U1") (pin "40") (pinfunction "PB4_40") (pintype "bidirectional"))
    )
    (net (code "54") (name "unconnected-(U1A-PB5-Pad41)") (class "Default")
      (node (ref "U1") (pin "41") (pinfunction "PB5_41") (pintype "bidirectional"))
    )
    (net (code "55") (name "unconnected-(U1A-PB8-Pad45)") (class "Default")
      (node (ref "U1") (pin "45") (pinfunction "PB8_45") (pintype "bidirectional"))
    )
    (net (code "56") (name "unconnected-(U1A-PB9-Pad46)") (class "Default")
      (node (ref "U1") (pin "46") (pinfunction "PB9_46") (pintype "bidirectional"))
    )
    (net (code "57") (name "unconnected-(U1A-PB14-Pad27)") (class "Default")
      (node (ref "U1") (pin "27") (pinfunction "PB14_27") (pintype "bidirectional"))
    )
    (net (code "58") (name "unconnected-(U1A-PC13-TAMPER-RTC-Pad2)") (class "Default")
      (node (ref "U1") (pin "2") (pinfunction "PC13-TAMPER-RTC_2") (pintype "bidirectional"))
    )
    (net (code "59") (name "unconnected-(U1A-PC14-OSC32_IN-Pad3)") (class "Default")
      (node (ref "U1") (pin "3") (pinfunction "PC14-OSC32_IN_3") (pintype "bidirectional"))
    )
    (net (code "60") (name "unconnected-(U1A-PC15-OSC32_OUT-Pad4)") (class "Default")
      (node (ref "U1") (pin "4") (pinfunction "PC15-OSC32_OUT_4") (pintype "bidirectional"))
    )
    (net (code "61") (name "unconnected-(U1A-PD0-OSC_IN-Pad5)") (class "Default")
      (node (ref "U1") (pin "5") (pinfunction "PD0-OSC_IN_5") (pintype "bidirectional"))
    )
    (net (code "62") (name "unconnected-(U1A-PD1-OSC_OUT-Pad6)") (class "Default")
      (node (ref "U1") (pin "6") (pinfunction "PD1-OSC_OUT_6") (pintype "bidirectional"))
    )
  )
)
